# ChargeDischargeSwitchingCircuit.net
KiCad netlist of a schematic drawn in EasyEDA Pro
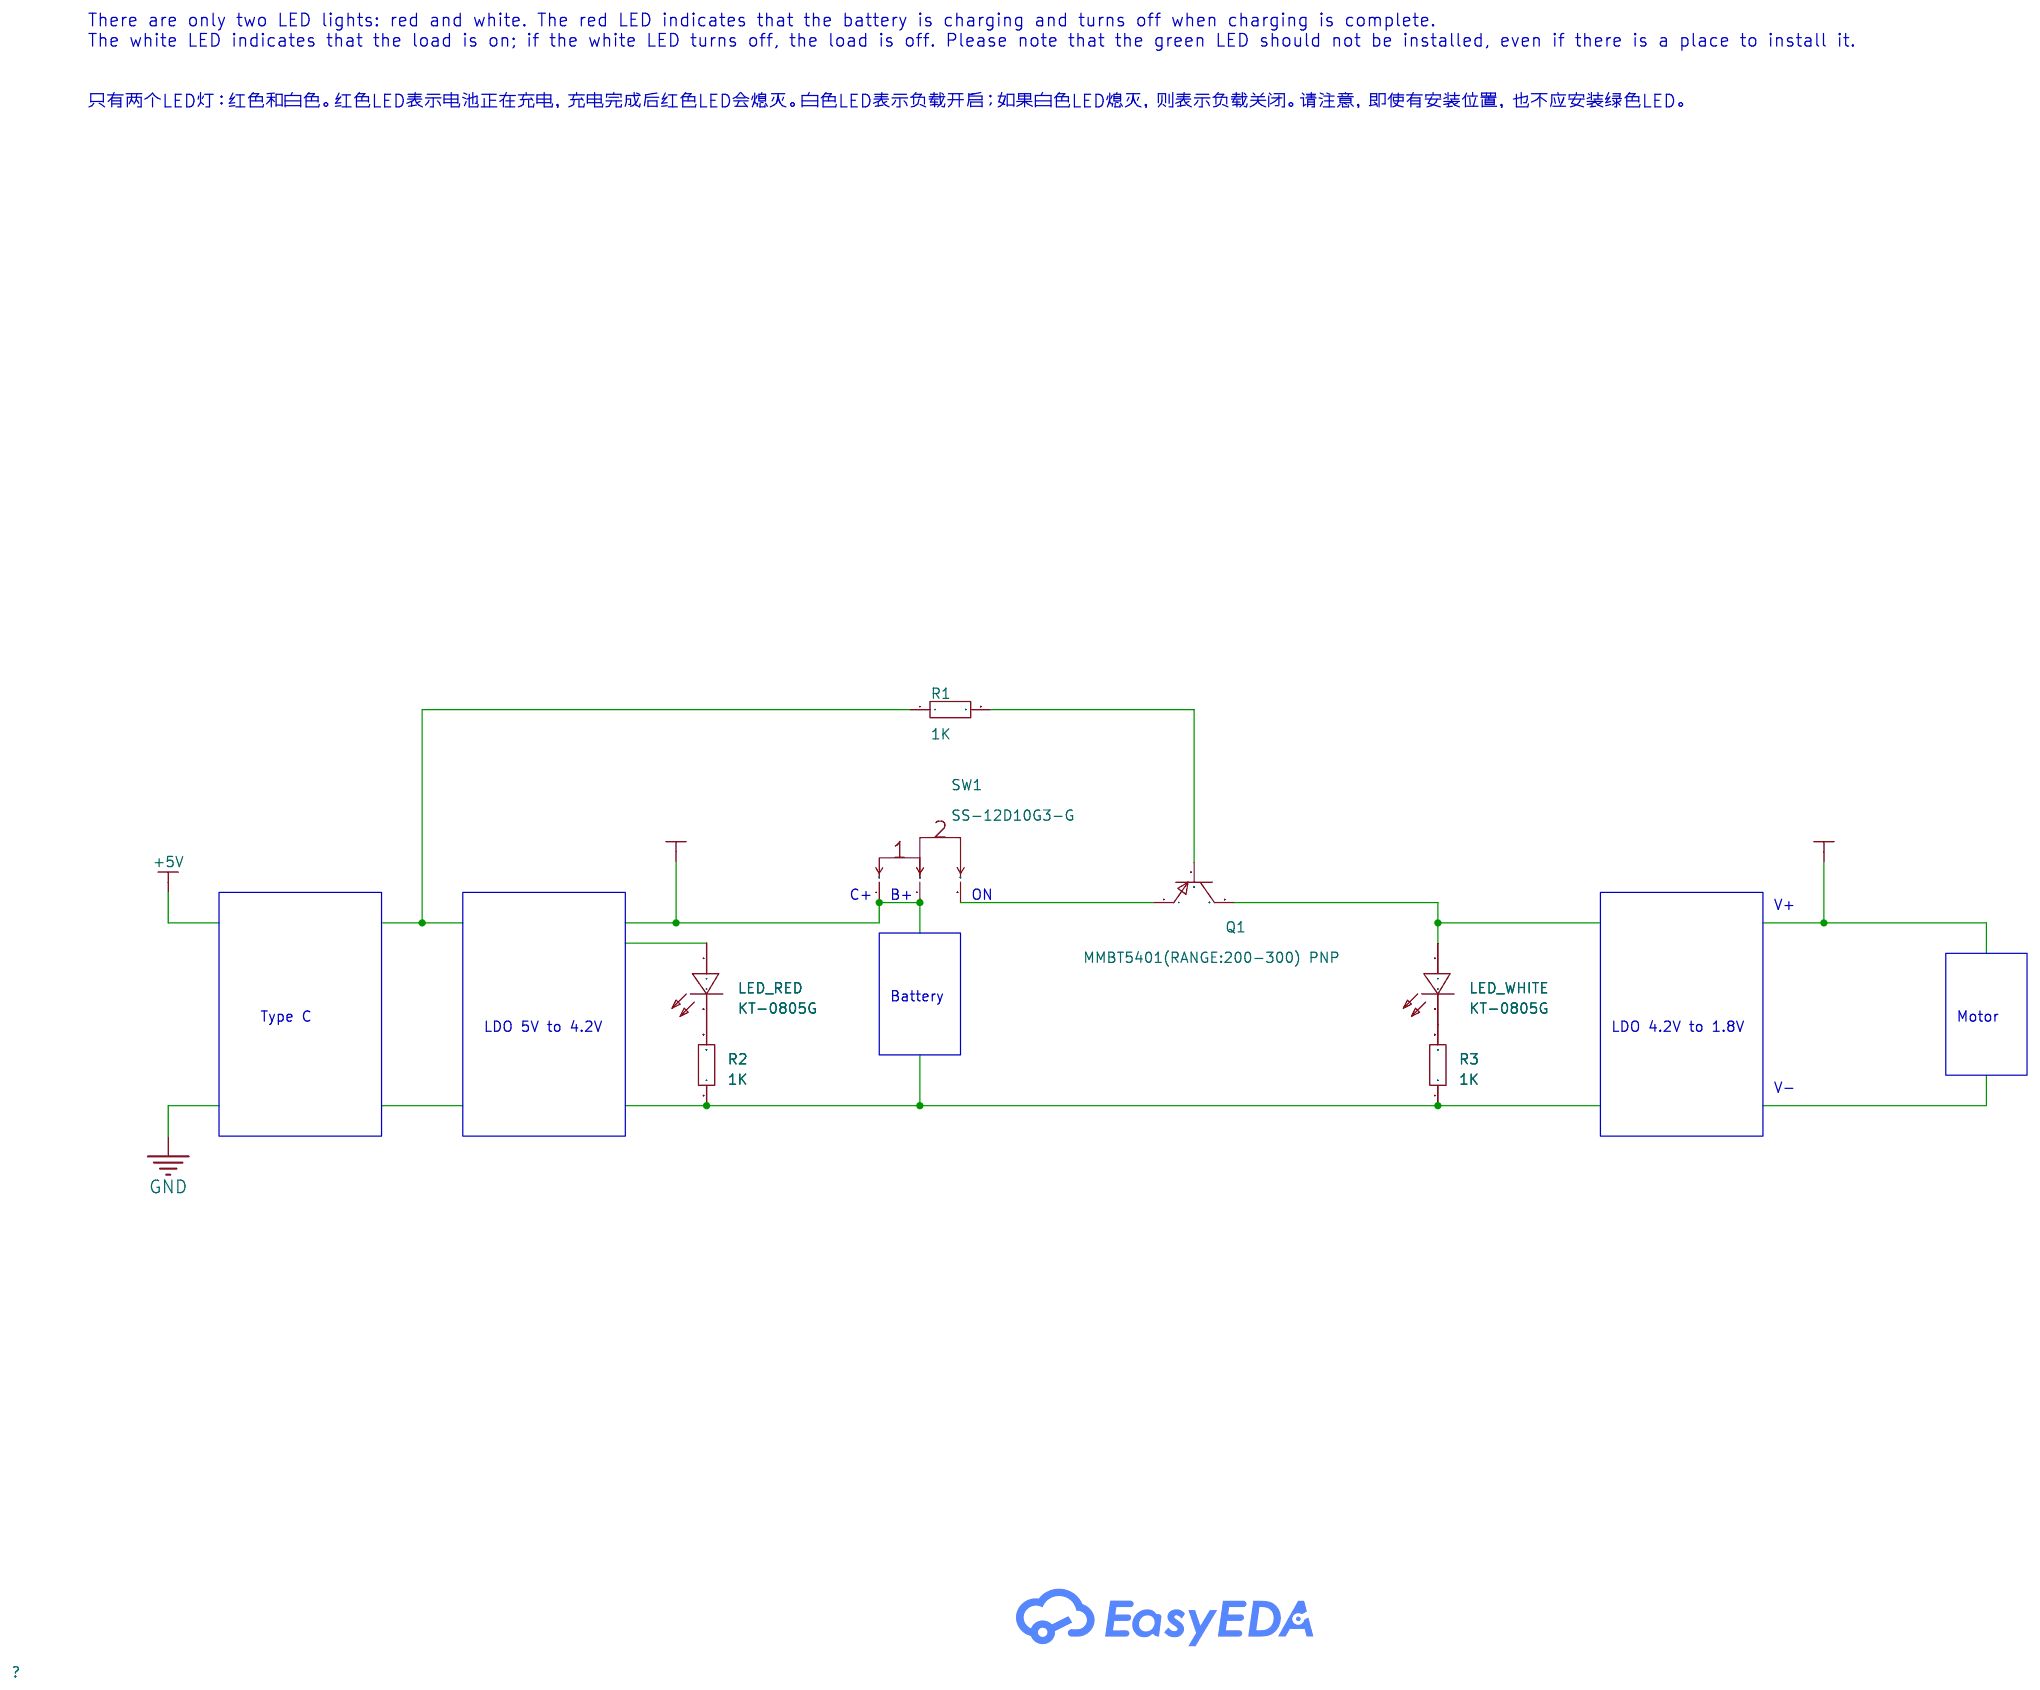
[diagram p0: schematic sheet]

(export (version "E")
  (design (tool "Eeschema 10.0.6"))
  (components
    (comp (ref "LED_RED")
      (value "KT-0805G")
      (footprint "easyedapro:LED0805-R-RD")
      (fields (field (name "Manufacturer") "KENTO"))
      (libsource (lib "easyedapro") (part "0805G (Green)"))
    )
    (comp (ref "LED_WHITE")
      (value "KT-0805G")
      (footprint "easyedapro:LED0805-R-RD")
      (fields (field (name "Manufacturer") "KENTO"))
      (libsource (lib "easyedapro") (part "0805G (Green)"))
    )
    (comp (ref "Q1")
      (value "MMBT5401(RANGE:200-300) PNP")
      (footprint "easyedapro:SOT-23-3_L2.9-W1.3-P1.90-LS2.4-BR")
      (fields (field (name "Manufacturer") "CJ(江苏长电/长晶)"))
      (libsource (lib "easyedapro") (part "MMBT5401"))
    )
    (comp (ref "R1") (value "1K") (footprint "easyedapro:R0603") (libsource (lib "easyedapro") (part "Res")))
    (comp (ref "R2") (value "1K") (footprint "easyedapro:R0603") (libsource (lib "easyedapro") (part "Res")))
    (comp (ref "R3") (value "1K") (footprint "easyedapro:R0603") (libsource (lib "easyedapro") (part "Res")))
    (comp (ref "SW1")
      (value "SS-12D10G3-G")
      (footprint "easyedapro:SW-TH_3P-L12.7-W6.7-P4.80_SS-12D10G10-G")
      (fields (field (name "Manufacturer") "XUNPU(讯普)"))
      (libsource (lib "easyedapro") (part "SS-12D10G3-G"))
    )
  )
  (nets
    (net (code "2") (name "+4.2V") (class "Default")
      (node (ref "SW1") (pin "1") (pinfunction "1_1") (pintype "unspecified"))
      (node (ref "SW1") (pin "2") (pinfunction "2_2") (pintype "unspecified"))
    )
    (net (code "5") (name "Net-(LED_RED-K)") (class "Default")
      (node (ref "LED_RED") (pin "2") (pinfunction "K_2") (pintype "unspecified"))
      (node (ref "R2") (pin "2") (pinfunction "2_2") (pintype "input"))
    )
    (net (code "6") (name "Net-(LED_WHITE-A)") (class "Default")
      (node (ref "LED_WHITE") (pin "1") (pinfunction "A_1") (pintype "unspecified"))
      (node (ref "Q1") (pin "3") (pinfunction "C_3") (pintype "unspecified"))
    )
    (net (code "7") (name "Net-(LED_WHITE-K)") (class "Default")
      (node (ref "LED_WHITE") (pin "2") (pinfunction "K_2") (pintype "unspecified"))
      (node (ref "R3") (pin "2") (pinfunction "2_2") (pintype "input"))
    )
    (net (code "8") (name "Net-(Q1-B)") (class "Default")
      (node (ref "Q1") (pin "1") (pinfunction "B_1") (pintype "unspecified"))
      (node (ref "R1") (pin "2") (pinfunction "2_2") (pintype "input"))
    )
    (net (code "9") (name "Net-(Q1-E)") (class "Default")
      (node (ref "Q1") (pin "2") (pinfunction "E_2") (pintype "unspecified"))
      (node (ref "SW1") (pin "3") (pinfunction "3_3") (pintype "unspecified"))
    )
    (net (code "10") (name "Net-(R2-Pad1)") (class "Default")
      (node (ref "R2") (pin "1") (pinfunction "1_1") (pintype "input"))
      (node (ref "R3") (pin "1") (pinfunction "1_1") (pintype "input"))
    )
    (net (code "11") (name "unconnected-(LED_RED-A-Pad1)") (class "Default")
      (node (ref "LED_RED") (pin "1") (pinfunction "A_1") (pintype "unspecified"))
    )
    (net (code "12") (name "unconnected-(R1-Pad1)") (class "Default")
      (node (ref "R1") (pin "1") (pinfunction "1_1") (pintype "input"))
    )
  )
)
